# Light.net
KiCad netlist of a schematic drawn in Altium Designer
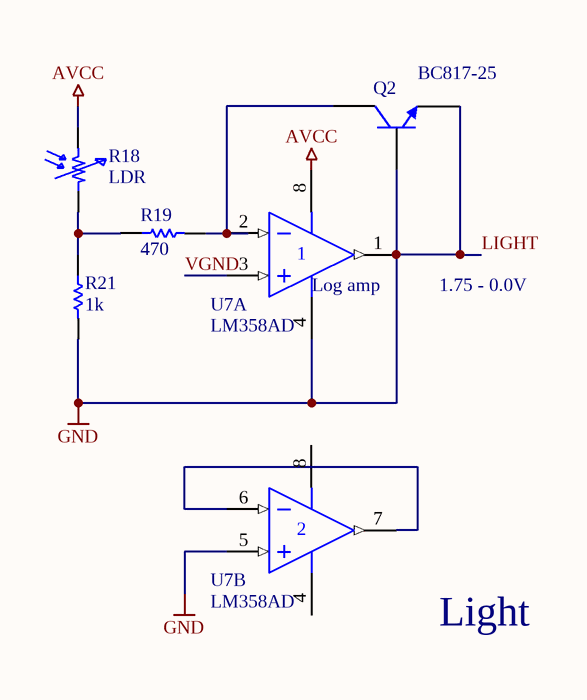
[diagram p0: Light.SchDoc]

(export (version "E")
  (design (tool "Eeschema 10.0.6"))
  (components
    (comp (ref "Q2")
      (value "BC817-25")
      (footprint "SOT23_N")
      (description "NPN General Purpose Amplifier")
      (fields (field (name "PUBLISHER") "Altium Limited"))
      (libsource (lib "FSC Discrete BJT") (part "BC817-25"))
    )
    (comp (ref "R18")
      (value "LDR")
      (footprint "KE-10720")
      (description "KE-10720")
      (libsource (lib "auxcomp") (part "LDR"))
    )
    (comp (ref "R19")
      (value "470")
      (footprint "6-0805")
      (fields (field (name "PUBLISHER") "Altium Limited"))
      (libsource (lib "Panasonic Resistor") (part "ERJ6RB"))
    )
    (comp (ref "R21")
      (value "1k")
      (footprint "6-0805")
      (fields (field (name "PUBLISHER") "Altium Limited"))
      (libsource (lib "Panasonic Resistor") (part "ERJ6RB"))
    )
    (comp (ref "U7")
      (value "LM358AD")
      (footprint "SOIC127P600X175-8AN")
      (description "Dual Operational Amplifier")
      (fields (field (name "PUBLISHER") "Altium Limited"))
      (libsource (lib "TI Operational Amplifier") (part "LM358AD"))
    )
  )
  (nets
    (net (code "1") (name "/VGND") (class "Default")
      (node (ref "U7") (pin "3") (pinfunction "IN+_3") (pintype "input"))
    )
    (net (code "2") (name "AVCC") (class "Default")
      (node (ref "R18") (pin "1") (pinfunction "1_1") (pintype "passive"))
      (node (ref "U7") (pin "8") (pinfunction "V+_8") (pintype "power_in"))
    )
    (net (code "3") (name "GND") (class "Default")
      (node (ref "Q2") (pin "1") (pinfunction "B_1") (pintype "passive"))
      (node (ref "Q2") (pin "2") (pinfunction "E_2") (pintype "passive"))
      (node (ref "R21") (pin "2") (pinfunction "2_2") (pintype "passive"))
      (node (ref "U7") (pin "1") (pinfunction "OUT_1") (pintype "output"))
      (node (ref "U7") (pin "4") (pinfunction "V-_4") (pintype "power_in"))
      (node (ref "U7") (pin "5") (pinfunction "IN+_5") (pintype "input"))
    )
    (net (code "4") (name "Net-(Q2-C)") (class "Default")
      (node (ref "Q2") (pin "3") (pinfunction "C_3") (pintype "passive"))
      (node (ref "R19") (pin "2") (pinfunction "2_2") (pintype "passive"))
      (node (ref "U7") (pin "2") (pinfunction "IN-_2") (pintype "input"))
    )
    (net (code "5") (name "Net-(R18-Pad2)") (class "Default")
      (node (ref "R18") (pin "2") (pinfunction "2_2") (pintype "passive"))
      (node (ref "R19") (pin "1") (pinfunction "1_1") (pintype "passive"))
      (node (ref "R21") (pin "1") (pinfunction "1_1") (pintype "passive"))
    )
    (net (code "6") (name "Net-(U7B-IN-)") (class "Default")
      (node (ref "U7") (pin "6") (pinfunction "IN-_6") (pintype "input"))
      (node (ref "U7") (pin "7") (pinfunction "OUT_7") (pintype "output"))
    )
    (net (code "7") (name "unconnected-(U7B-V+-Pad8)") (class "Default")
      (node (ref "U7") (pin "8") (pinfunction "V+_8") (pintype "power_in"))
    )
    (net (code "8") (name "unconnected-(U7B-V--Pad4)") (class "Default")
      (node (ref "U7") (pin "4") (pinfunction "V-_4") (pintype "power_in"))
    )
  )
)
